# Themistor_Breakout.net
KiCad netlist of a schematic drawn in EAGLE
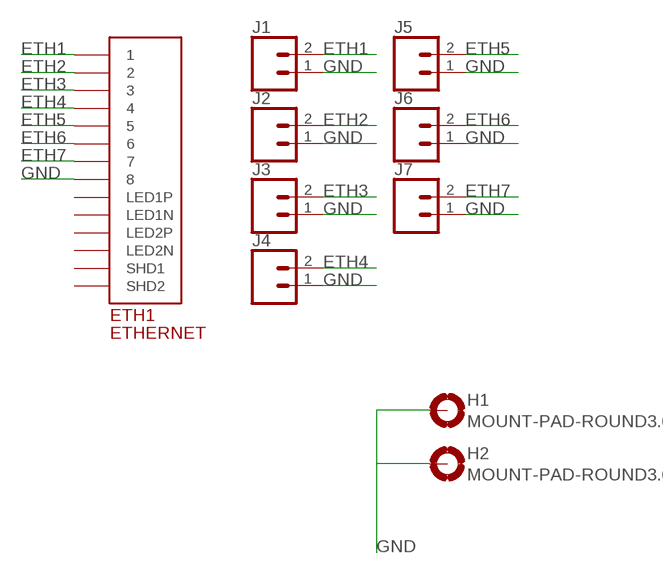
[diagram p0: schematic, sheet 1]

(export (version "E")
  (design (tool "Eeschema 10.0.6"))
  (components
    (comp (ref "ETH1")
      (value "ETHERNET")
      (footprint "eagle-import:A122645-ND")
      (libsource (lib "eagle-import") (part "ETHERNET"))
    )
    (comp (ref "H1")
      (value "MOUNT-PAD-ROUND3.6")
      (footprint "eagle-import:3,6-PAD")
      (libsource (lib "eagle-import") (part "MOUNT-PAD-ROUND3.6"))
    )
    (comp (ref "H2")
      (value "MOUNT-PAD-ROUND3.6")
      (footprint "eagle-import:3,6-PAD")
      (libsource (lib "eagle-import") (part "MOUNT-PAD-ROUND3.6"))
    )
    (comp (ref "J1")
      (value "CONN_023.5MM")
      (footprint "eagle-import:SCREWTERMINAL-3.5MM-2")
      (libsource (lib "eagle-import") (part "CONN_023.5MM"))
    )
    (comp (ref "J2")
      (value "CONN_023.5MM")
      (footprint "eagle-import:SCREWTERMINAL-3.5MM-2")
      (libsource (lib "eagle-import") (part "CONN_023.5MM"))
    )
    (comp (ref "J3")
      (value "CONN_023.5MM")
      (footprint "eagle-import:SCREWTERMINAL-3.5MM-2")
      (libsource (lib "eagle-import") (part "CONN_023.5MM"))
    )
    (comp (ref "J4")
      (value "CONN_023.5MM")
      (footprint "eagle-import:SCREWTERMINAL-3.5MM-2")
      (libsource (lib "eagle-import") (part "CONN_023.5MM"))
    )
    (comp (ref "J5")
      (value "CONN_023.5MM")
      (footprint "eagle-import:SCREWTERMINAL-3.5MM-2")
      (libsource (lib "eagle-import") (part "CONN_023.5MM"))
    )
    (comp (ref "J6")
      (value "CONN_023.5MM")
      (footprint "eagle-import:SCREWTERMINAL-3.5MM-2")
      (libsource (lib "eagle-import") (part "CONN_023.5MM"))
    )
    (comp (ref "J7")
      (value "CONN_023.5MM")
      (footprint "eagle-import:SCREWTERMINAL-3.5MM-2")
      (libsource (lib "eagle-import") (part "CONN_023.5MM"))
    )
  )
  (nets
    (net (code "1") (name "/ETH1") (class "Default")
      (node (ref "ETH1") (pin "P$1") (pinfunction "1_P$1") (pintype "bidirectional"))
      (node (ref "J1") (pin "2") (pinfunction "2_2") (pintype "passive"))
    )
    (net (code "2") (name "/ETH2") (class "Default")
      (node (ref "ETH1") (pin "P$2") (pinfunction "2_P$2") (pintype "bidirectional"))
      (node (ref "J2") (pin "2") (pinfunction "2_2") (pintype "passive"))
    )
    (net (code "3") (name "/ETH3") (class "Default")
      (node (ref "ETH1") (pin "P$3") (pinfunction "3_P$3") (pintype "bidirectional"))
      (node (ref "J3") (pin "2") (pinfunction "2_2") (pintype "passive"))
    )
    (net (code "4") (name "/ETH4") (class "Default")
      (node (ref "ETH1") (pin "P$4") (pinfunction "4_P$4") (pintype "bidirectional"))
      (node (ref "J4") (pin "2") (pinfunction "2_2") (pintype "passive"))
    )
    (net (code "5") (name "/ETH5") (class "Default")
      (node (ref "ETH1") (pin "P$5") (pinfunction "5_P$5") (pintype "bidirectional"))
      (node (ref "J5") (pin "2") (pinfunction "2_2") (pintype "passive"))
    )
    (net (code "6") (name "/ETH6") (class "Default")
      (node (ref "ETH1") (pin "P$6") (pinfunction "6_P$6") (pintype "bidirectional"))
      (node (ref "J6") (pin "2") (pinfunction "2_2") (pintype "passive"))
    )
    (net (code "7") (name "/ETH7") (class "Default")
      (node (ref "ETH1") (pin "P$7") (pinfunction "7_P$7") (pintype "bidirectional"))
      (node (ref "J7") (pin "2") (pinfunction "2_2") (pintype "passive"))
    )
    (net (code "8") (name "/GND") (class "Default")
      (node (ref "ETH1") (pin "P$8") (pinfunction "8_P$8") (pintype "bidirectional"))
      (node (ref "H1") (pin "B3,6") (pinfunction "MOUNT_B3,6") (pintype "passive"))
      (node (ref "H2") (pin "B3,6") (pinfunction "MOUNT_B3,6") (pintype "passive"))
      (node (ref "J1") (pin "1") (pinfunction "1_1") (pintype "passive"))
      (node (ref "J2") (pin "1") (pinfunction "1_1") (pintype "passive"))
      (node (ref "J3") (pin "1") (pinfunction "1_1") (pintype "passive"))
      (node (ref "J4") (pin "1") (pinfunction "1_1") (pintype "passive"))
      (node (ref "J5") (pin "1") (pinfunction "1_1") (pintype "passive"))
      (node (ref "J6") (pin "1") (pinfunction "1_1") (pintype "passive"))
      (node (ref "J7") (pin "1") (pinfunction "1_1") (pintype "passive"))
    )
    (net (code "9") (name "unconnected-(ETH1-LED1N-PadP$9)") (class "Default")
      (node (ref "ETH1") (pin "P$9") (pinfunction "LED1N_P$9") (pintype "bidirectional"))
    )
    (net (code "10") (name "unconnected-(ETH1-LED1P-PadP$10)") (class "Default")
      (node (ref "ETH1") (pin "P$10") (pinfunction "LED1P_P$10") (pintype "bidirectional"))
    )
    (net (code "11") (name "unconnected-(ETH1-LED2N-PadP$11)") (class "Default")
      (node (ref "ETH1") (pin "P$11") (pinfunction "LED2N_P$11") (pintype "bidirectional"))
    )
    (net (code "12") (name "unconnected-(ETH1-LED2P-PadP$12)") (class "Default")
      (node (ref "ETH1") (pin "P$12") (pinfunction "LED2P_P$12") (pintype "bidirectional"))
    )
    (net (code "13") (name "unconnected-(ETH1-SHD1-PadP$13)") (class "Default")
      (node (ref "ETH1") (pin "P$13") (pinfunction "SHD1_P$13") (pintype "bidirectional"))
    )
    (net (code "14") (name "unconnected-(ETH1-SHD2-PadP$14)") (class "Default")
      (node (ref "ETH1") (pin "P$14") (pinfunction "SHD2_P$14") (pintype "bidirectional"))
    )
  )
)
